# SCH_hacker-card_2024-07-10.net
KiCad netlist of a schematic drawn in EasyEDA
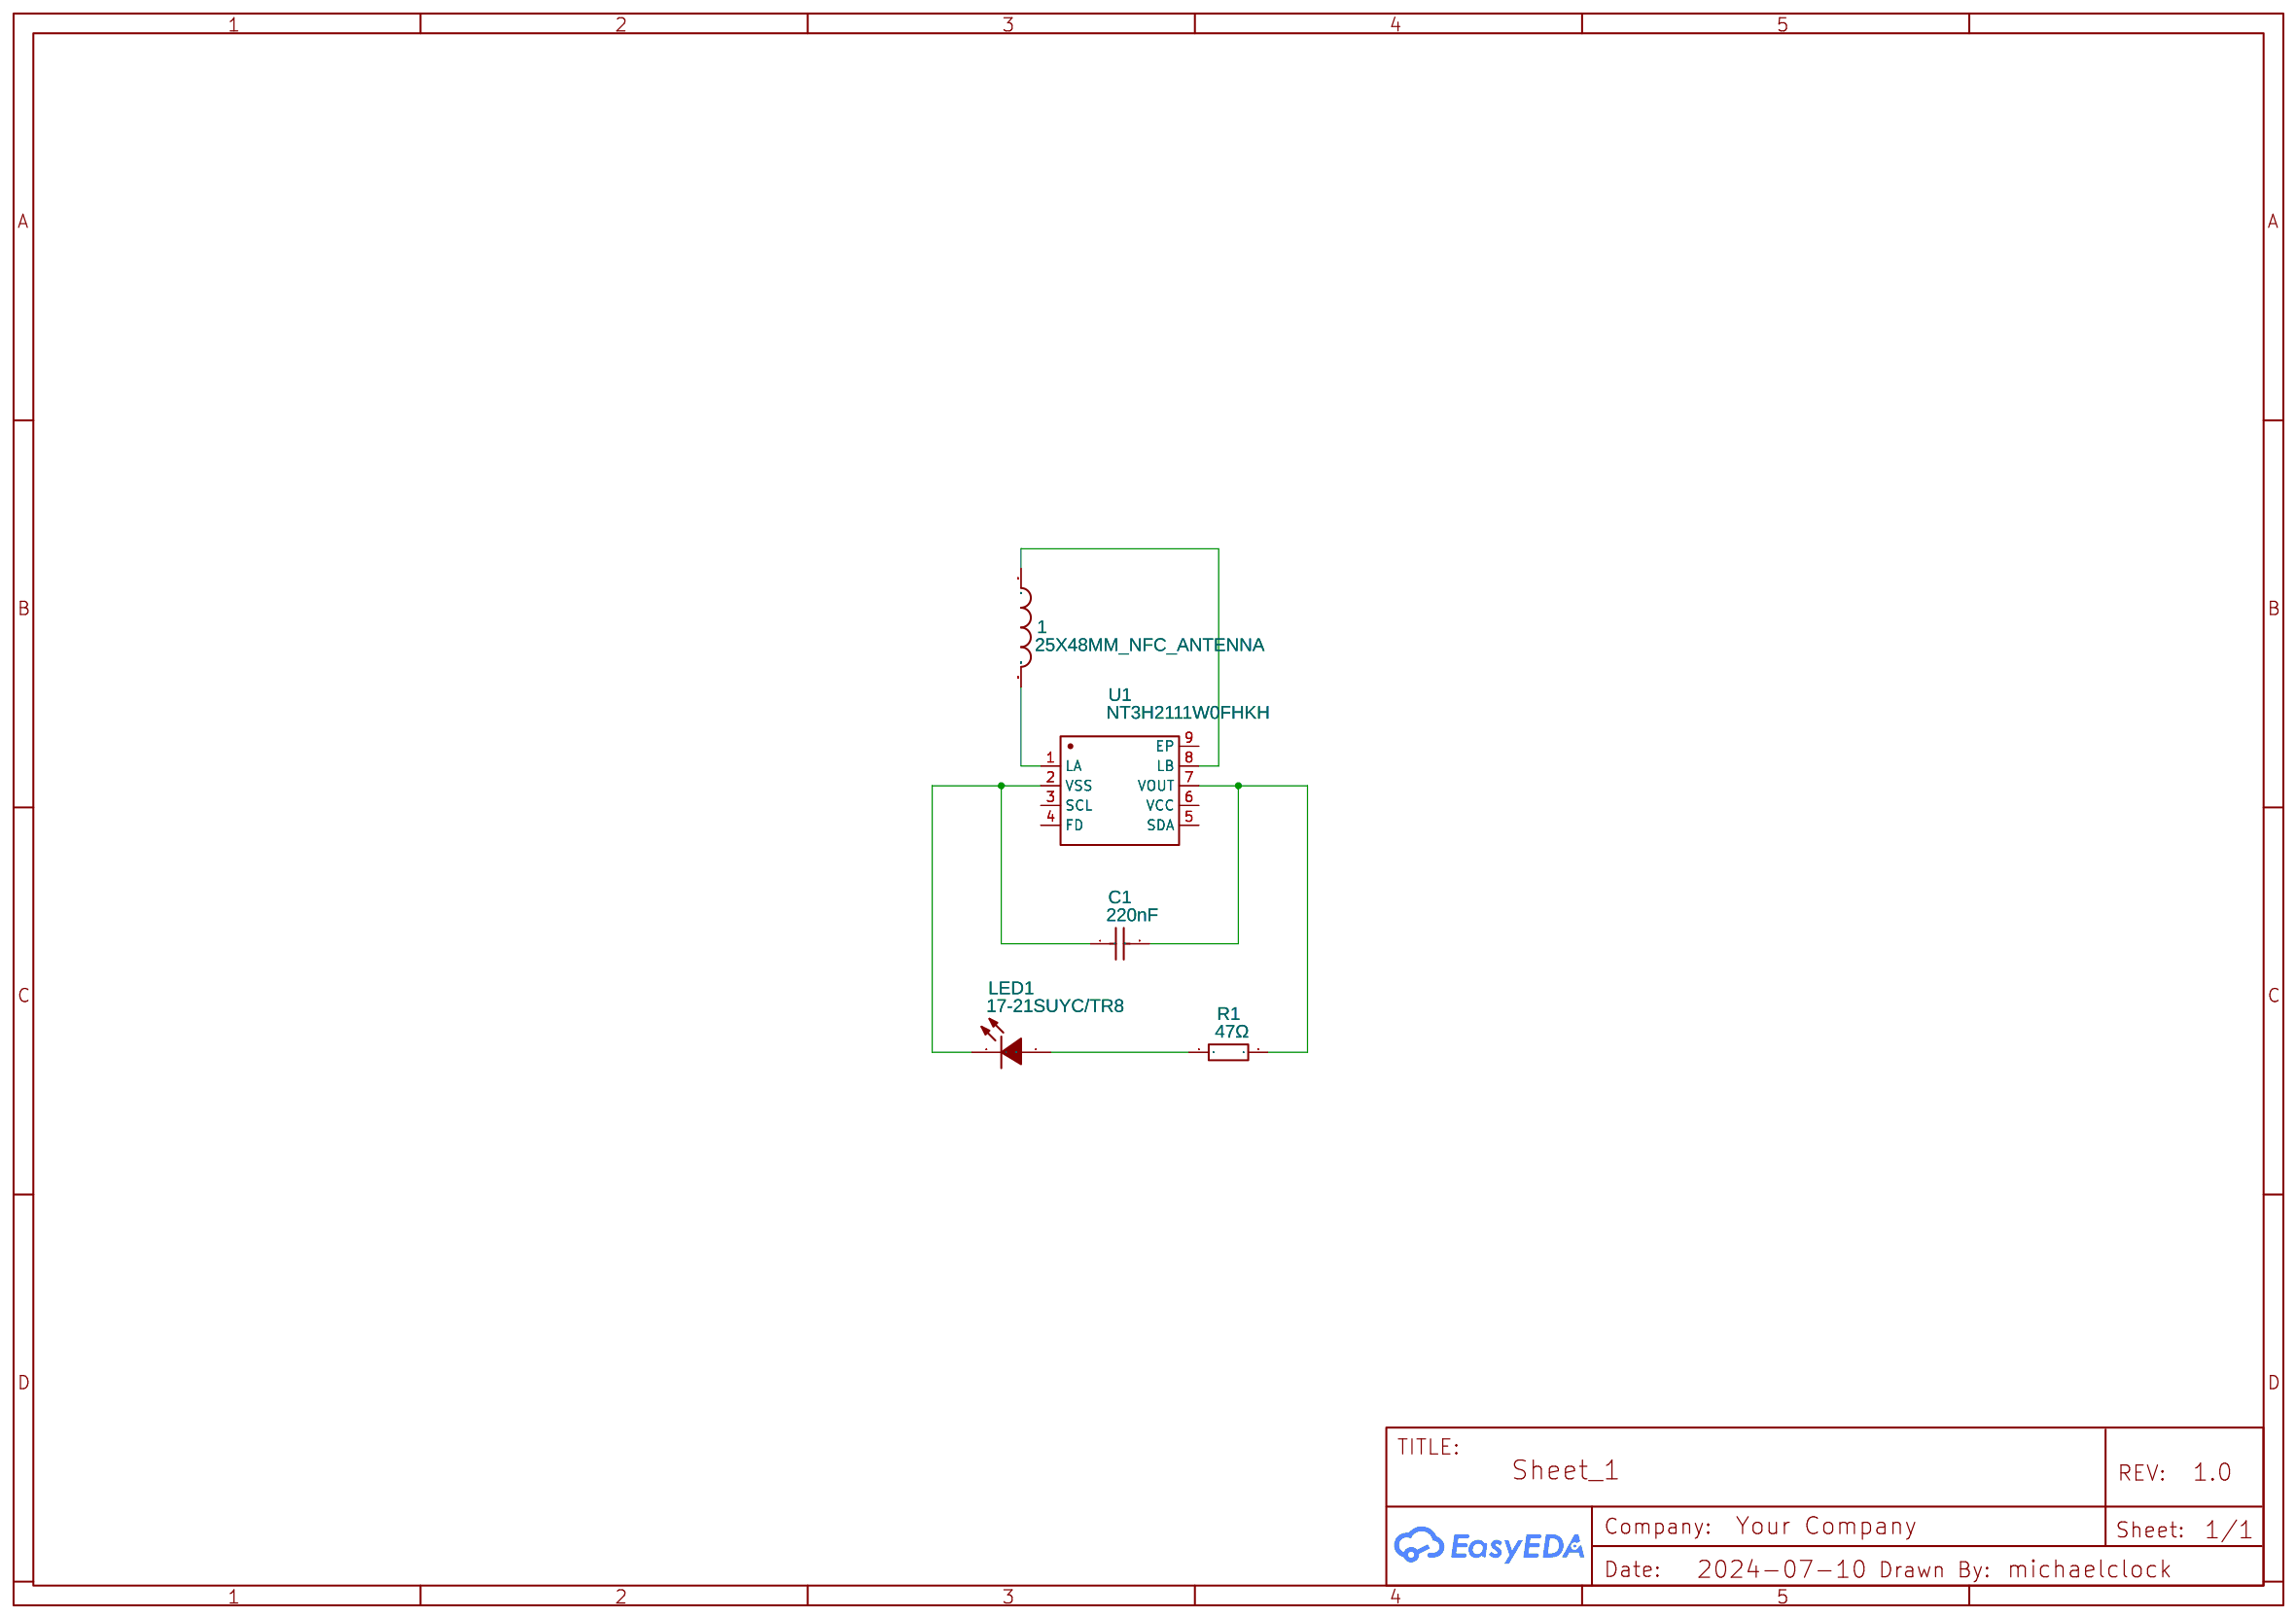
[diagram p0: schematic sheet]

(export (version "E")
  (design (tool "Eeschema 10.0.6"))
  (components
    (comp (ref "1") (value "25X48MM_NFC_ANTENNA") (libsource (lib "") (part "25X48MM_NFC_ANTENNA")))
    (comp (ref "C1")
      (value "220nF")
      (fields
        (field (name "Manufacturer Part") "CL10B224KA8NNNC")
        (field (name "Manufacturer") "SAMSUNG(三星)")
      )
      (libsource (lib "") (part "CL10B224KA8NNNC"))
    )
    (comp (ref "LED1")
      (value "17-21SUYC/TR8")
      (fields (field (name "Manufacturer Part") "KT-0805黄灯") (field (name "Manufacturer") "KENTO"))
      (libsource (lib "") (part "17-21SUYC/TR8"))
    )
    (comp (ref "R1")
      (value "47Ω")
      (fields
        (field (name "Manufacturer Part") "0603WAF470JT5E")
        (field (name "Manufacturer") "UNI-ROYAL(厚声)")
      )
      (libsource (lib "") (part "0603WAF470JT5E"))
    )
    (comp (ref "U1")
      (value "NT3H2111W0FHKH")
      (fields (field (name "Manufacturer") "NXP(恩智浦)"))
      (libsource (lib "") (part "NT3H2111W0FHKH"))
    )
  )
  (nets
    (net (code "1") (name "Net-(LED1-+)") (class "Default")
      (node (ref "LED1") (pin "1") (pinfunction "+_1") (pintype "unspecified"))
      (node (ref "R1") (pin "1") (pinfunction "1_1") (pintype "input"))
    )
    (net (code "2") (name "Net-(LED1--)") (class "Default")
      (node (ref "C1") (pin "1") (pinfunction "1_1") (pintype "input"))
      (node (ref "LED1") (pin "2") (pinfunction "-_2") (pintype "unspecified"))
      (node (ref "U1") (pin "2") (pinfunction "VSS_2") (pintype "unspecified"))
    )
    (net (code "3") (name "Net-(U1-LA)") (class "Default")
      (node (ref "1") (pin "P$2") (pinfunction "P$2_P$2") (pintype "bidirectional"))
      (node (ref "U1") (pin "1") (pinfunction "LA_1") (pintype "unspecified"))
    )
    (net (code "4") (name "Net-(U1-LB)") (class "Default")
      (node (ref "1") (pin "P$1") (pinfunction "P$1_P$1") (pintype "bidirectional"))
      (node (ref "U1") (pin "8") (pinfunction "LB_8") (pintype "unspecified"))
    )
    (net (code "5") (name "Net-(U1-VOUT)") (class "Default")
      (node (ref "C1") (pin "2") (pinfunction "2_2") (pintype "input"))
      (node (ref "R1") (pin "2") (pinfunction "2_2") (pintype "input"))
      (node (ref "U1") (pin "7") (pinfunction "VOUT_7") (pintype "unspecified"))
    )
    (net (code "6") (name "unconnected-(U1-EP-Pad9)") (class "Default")
      (node (ref "U1") (pin "9") (pinfunction "EP_9") (pintype "unspecified"))
    )
    (net (code "7") (name "unconnected-(U1-FD-Pad4)") (class "Default")
      (node (ref "U1") (pin "4") (pinfunction "FD_4") (pintype "unspecified"))
    )
    (net (code "8") (name "unconnected-(U1-SCL-Pad3)") (class "Default")
      (node (ref "U1") (pin "3") (pinfunction "SCL_3") (pintype "unspecified"))
    )
    (net (code "9") (name "unconnected-(U1-SDA-Pad5)") (class "Default")
      (node (ref "U1") (pin "5") (pinfunction "SDA_5") (pintype "unspecified"))
    )
    (net (code "10") (name "unconnected-(U1-VCC-Pad6)") (class "Default")
      (node (ref "U1") (pin "6") (pinfunction "VCC_6") (pintype "unspecified"))
    )
  )
)
